# MD201__1.net
KiCad netlist of a schematic drawn in EAGLE
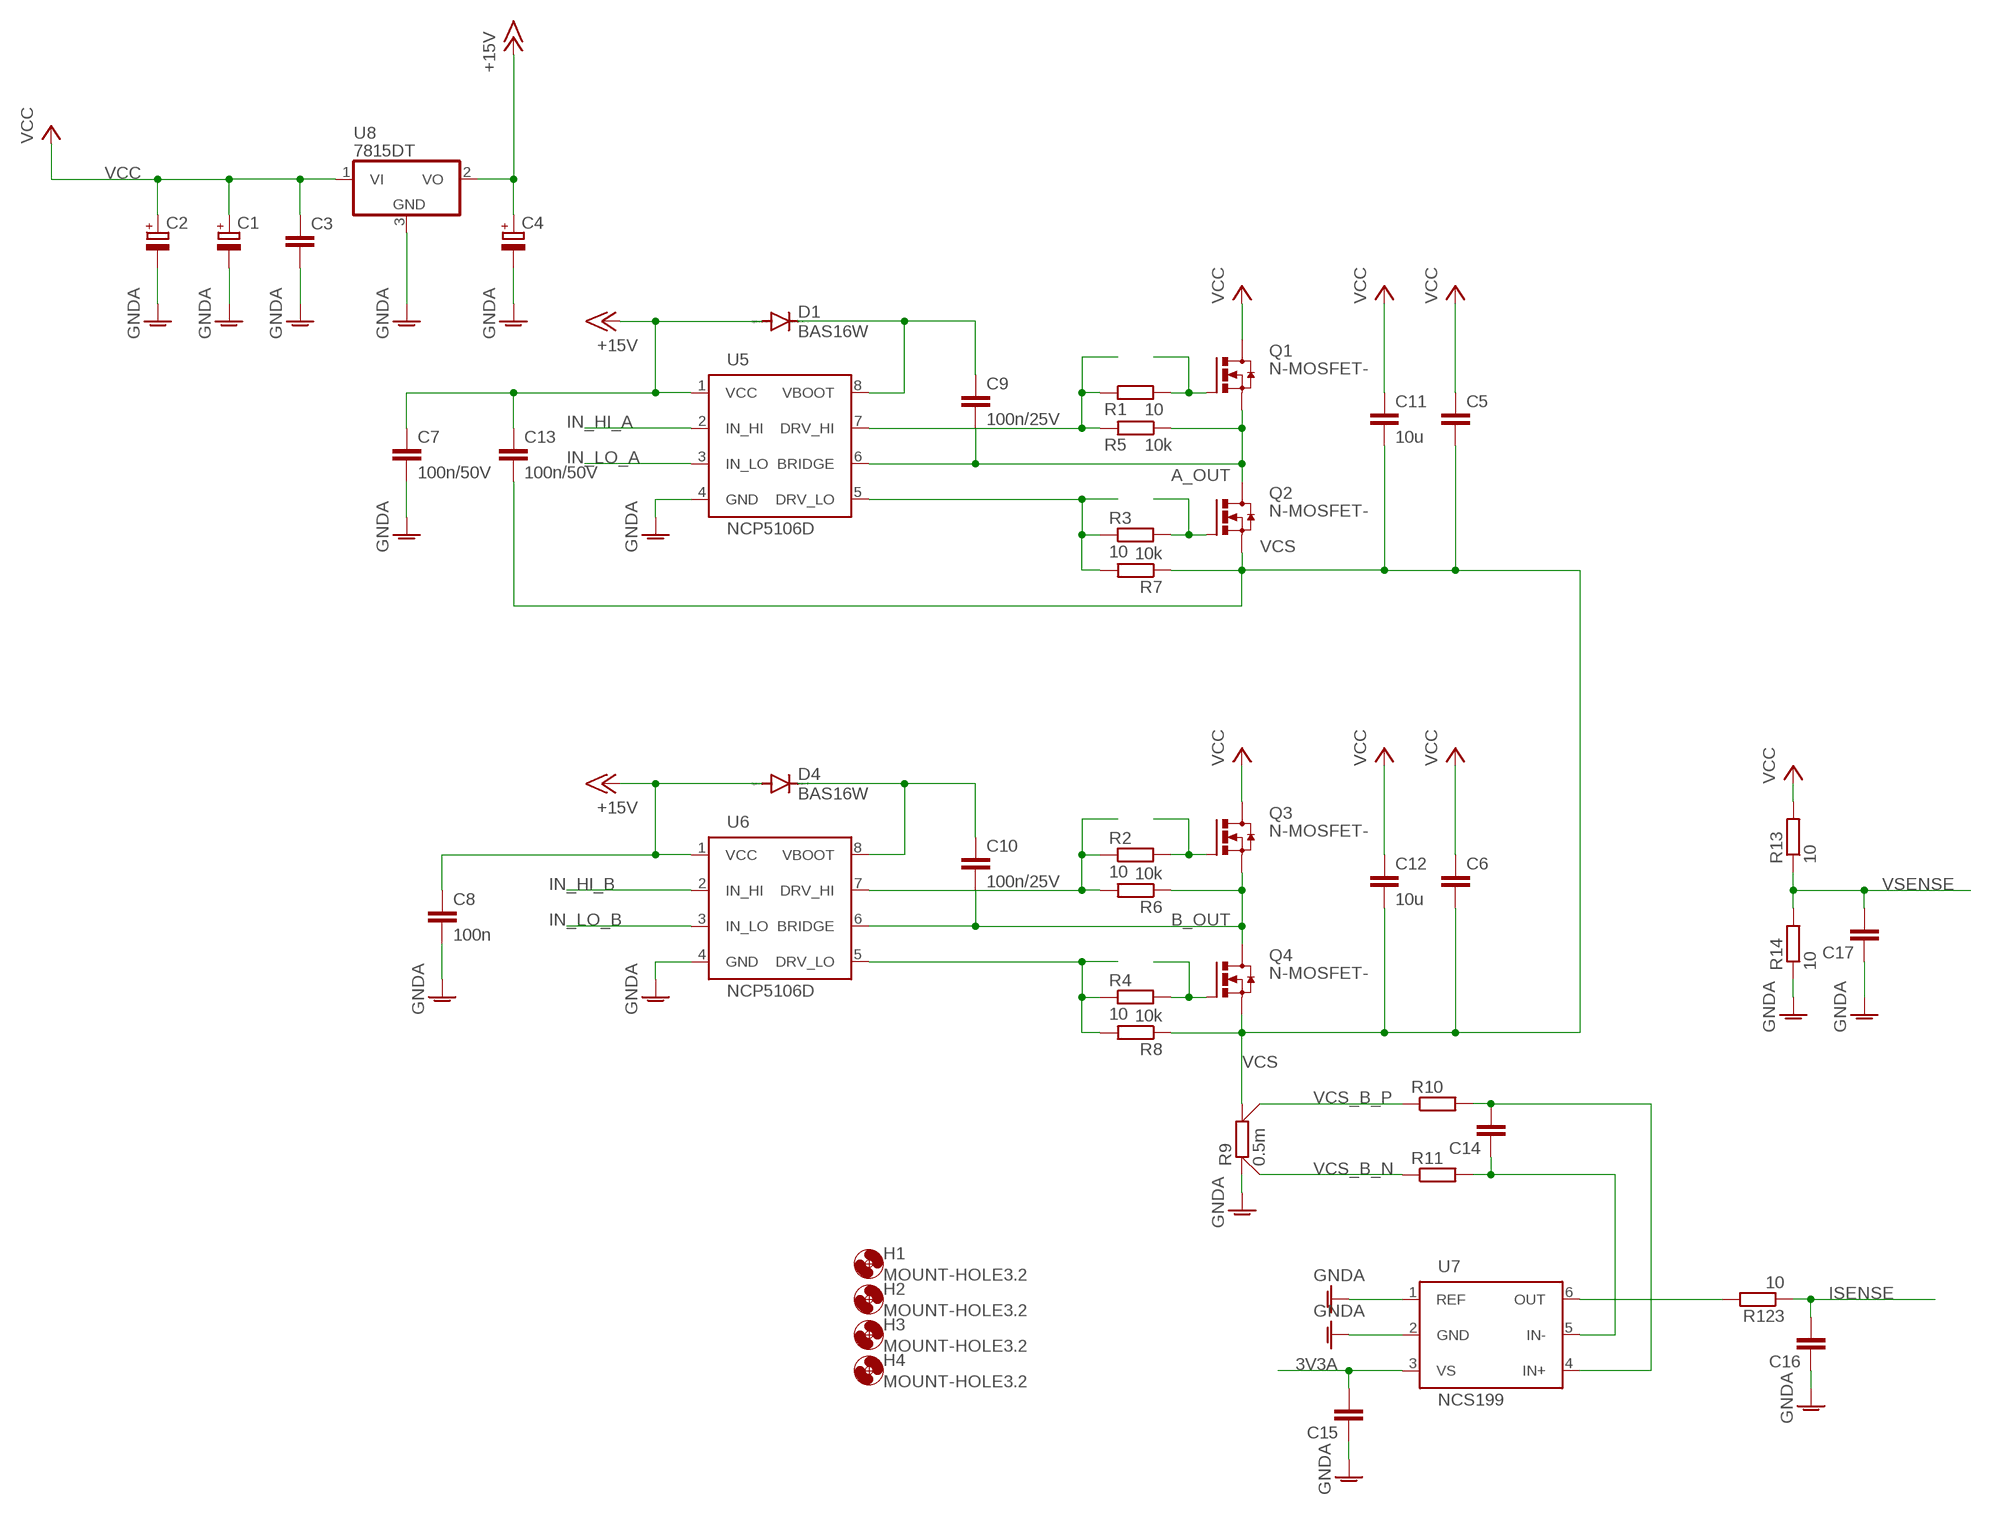
[diagram p0: schematic, sheet 1]
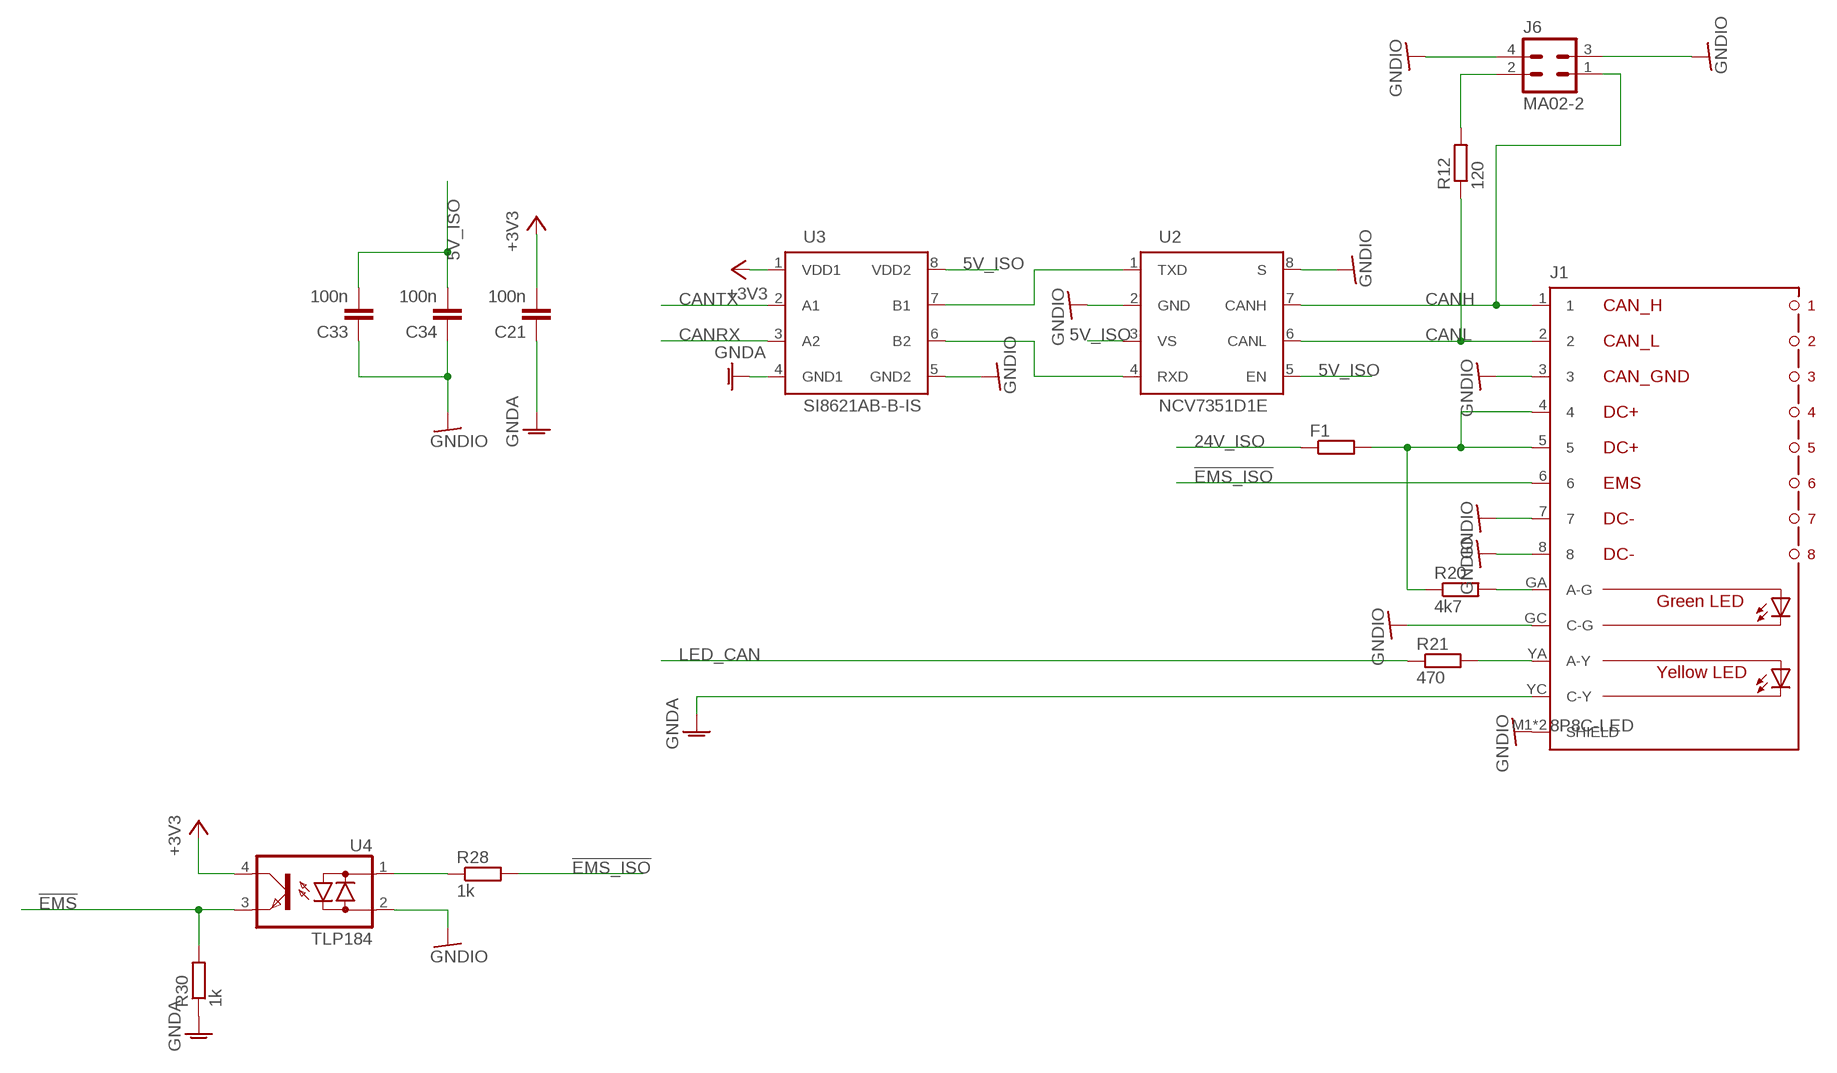
[diagram p1: schematic, sheet 2]
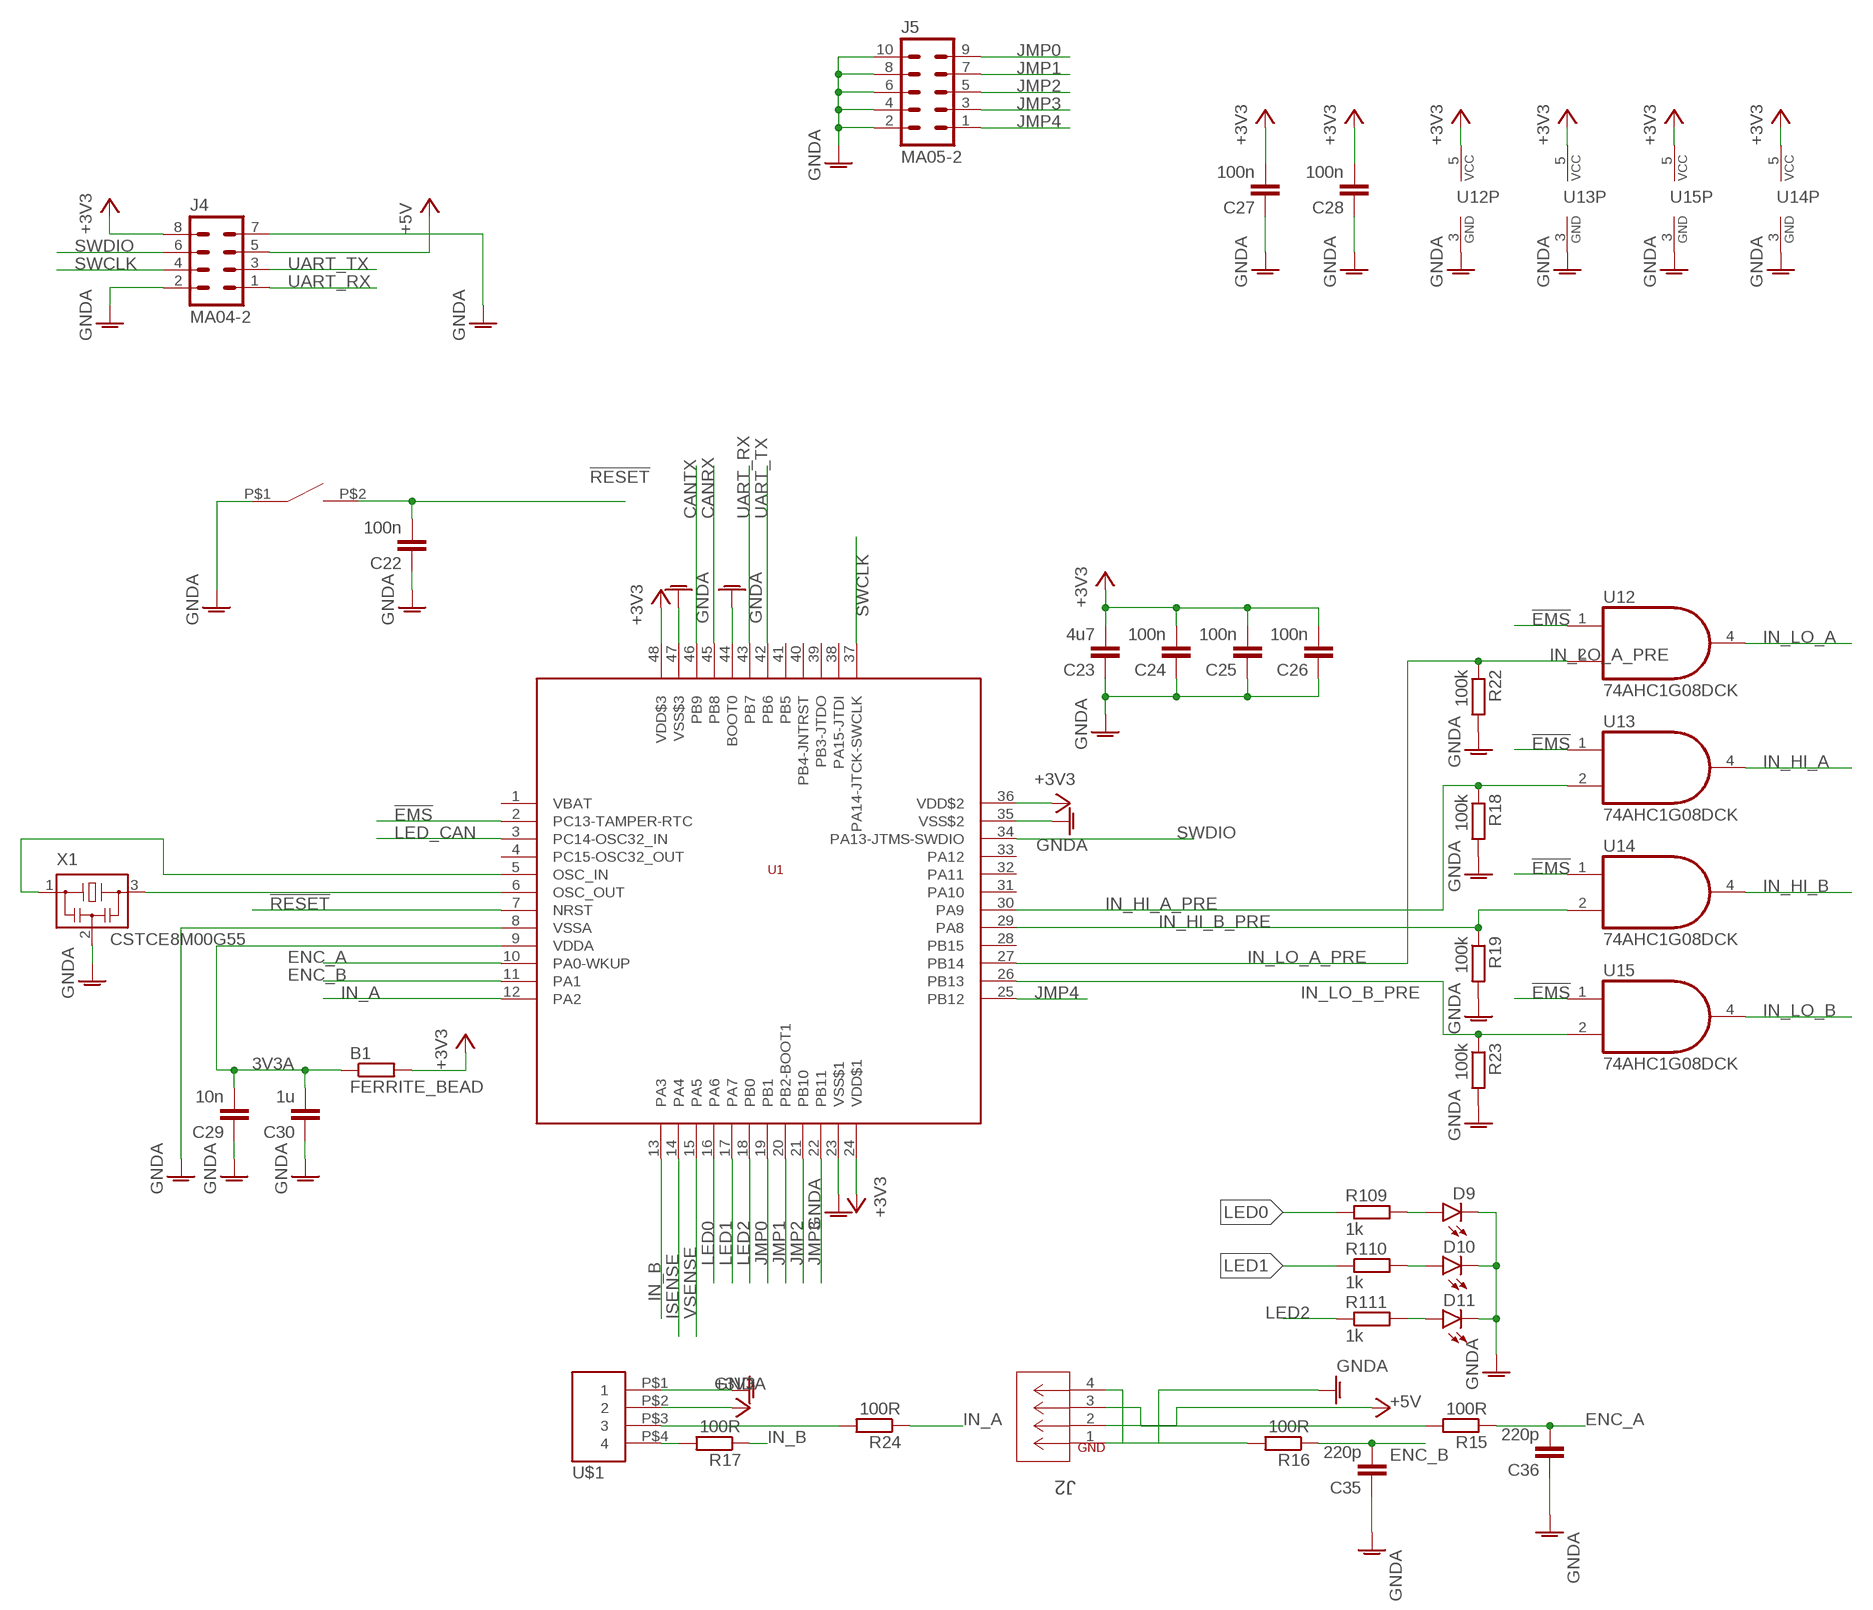
[diagram p2: schematic, sheet 3]
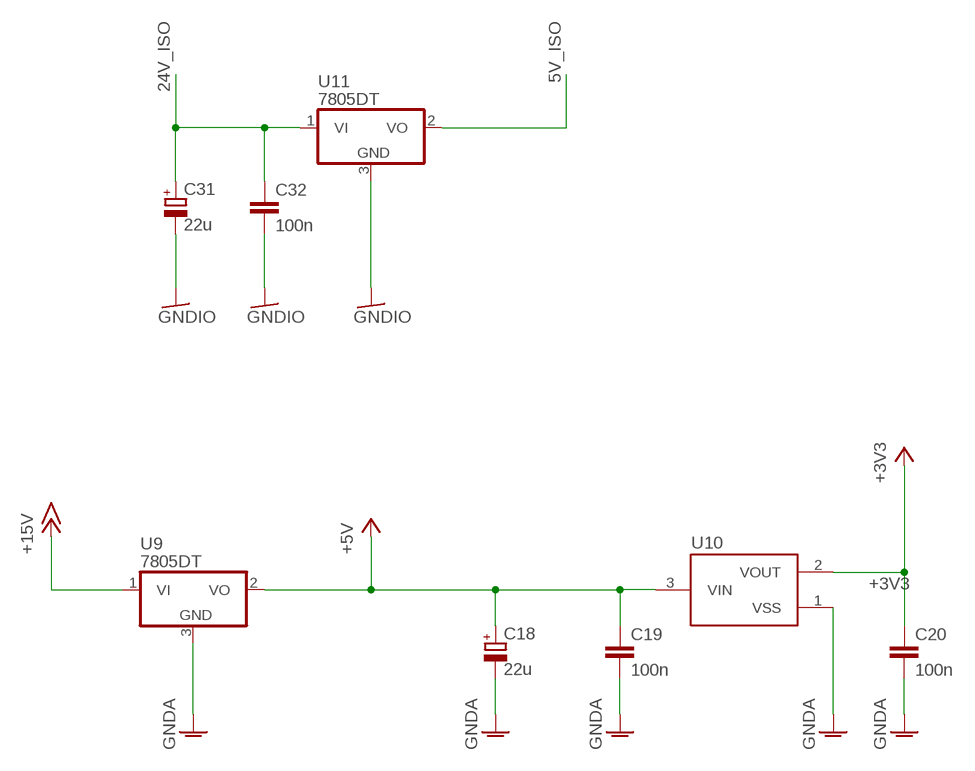
[diagram p3: schematic, sheet 4]

(export (version "E")
  (design (tool "Eeschema 10.0.6"))
  (components
    (comp (ref "C21")
      (value "100n")
      (footprint "eagle-import:C0603")
      (libsource (lib "eagle-import") (part "C-EUC0603"))
    )
    (comp (ref "C33")
      (value "100n")
      (footprint "eagle-import:C0805")
      (libsource (lib "eagle-import") (part "C-EUC0805"))
    )
    (comp (ref "C34")
      (value "100n")
      (footprint "eagle-import:C0603")
      (libsource (lib "eagle-import") (part "C-EUC0603"))
    )
    (comp (ref "F1")
      (value "R-EU_R1206")
      (footprint "eagle-import:R1206")
      (libsource (lib "eagle-import") (part "rcl_334_R-EU_R1206"))
    )
    (comp (ref "J1")
      (value "8P8C-LED")
      (footprint "eagle-import:8P8C-LED")
      (libsource (lib "eagle-import") (part "8P8C-LED"))
    )
    (comp (ref "J6")
      (value "MA02-2")
      (footprint "eagle-import:MA02-2W")
      (libsource (lib "eagle-import") (part "MA02-2"))
    )
    (comp (ref "R12")
      (value "120")
      (footprint "eagle-import:R0603")
      (libsource (lib "eagle-import") (part "rcl_334_R-EU_R0603"))
    )
    (comp (ref "R20")
      (value "4k7")
      (footprint "eagle-import:R0603")
      (libsource (lib "eagle-import") (part "rcl_334_R-EU_R0603"))
    )
    (comp (ref "R21")
      (value "470")
      (footprint "eagle-import:R0603")
      (libsource (lib "eagle-import") (part "rcl_334_R-EU_R0603"))
    )
    (comp (ref "R28")
      (value "1k")
      (footprint "eagle-import:R0603")
      (libsource (lib "eagle-import") (part "rcl_334_R-EU_R0603"))
    )
    (comp (ref "R30")
      (value "1k")
      (footprint "eagle-import:R0603")
      (libsource (lib "eagle-import") (part "rcl_334_R-EU_R0603"))
    )
    (comp (ref "U2")
      (value "NCV7351D1E")
      (footprint "eagle-import:SO08")
      (libsource (lib "eagle-import") (part "NCV7351D1E"))
    )
    (comp (ref "U3")
      (value "SI8621AB-B-IS")
      (footprint "eagle-import:SO08")
      (libsource (lib "eagle-import") (part "SI8621AB-B-IS"))
    )
    (comp (ref "U4")
      (value "TLP184")
      (footprint "eagle-import:11-4M1S")
      (libsource (lib "eagle-import") (part "TLP184"))
    )
    (comp (ref "C18")
      (value "22u")
      (footprint "eagle-import:E2,5-5")
      (libsource (lib "eagle-import") (part "CPOL-EUE2.5-5"))
    )
    (comp (ref "C19")
      (value "100n")
      (footprint "eagle-import:C0603")
      (libsource (lib "eagle-import") (part "C-EUC0603"))
    )
    (comp (ref "C20")
      (value "100n")
      (footprint "eagle-import:C0603")
      (libsource (lib "eagle-import") (part "C-EUC0603"))
    )
    (comp (ref "C31")
      (value "22u")
      (footprint "eagle-import:E2,5-5")
      (libsource (lib "eagle-import") (part "CPOL-EUE2.5-5"))
    )
    (comp (ref "C32")
      (value "100n")
      (footprint "eagle-import:C0603")
      (libsource (lib "eagle-import") (part "C-EUC0603"))
    )
    (comp (ref "U9")
      (value "7805DT")
      (footprint "eagle-import:TO252")
      (libsource (lib "eagle-import") (part "78DT05"))
    )
    (comp (ref "U10")
      (value "XC6206")
      (footprint "eagle-import:SOT95P240X110-3")
      (libsource (lib "eagle-import") (part "XC6206"))
    )
    (comp (ref "U11")
      (value "7805DT")
      (footprint "eagle-import:TO252")
      (libsource (lib "eagle-import") (part "78DT05"))
    )
    (comp (ref "B1")
      (value "FERRITE_BEAD")
      (footprint "eagle-import:R0603")
      (libsource (lib "eagle-import") (part "R-EU_R0603"))
    )
    (comp (ref "C22")
      (value "100n")
      (footprint "eagle-import:C0603")
      (libsource (lib "eagle-import") (part "C-EUC0603"))
    )
    (comp (ref "C23")
      (value "4u7")
      (footprint "eagle-import:C0805")
      (libsource (lib "eagle-import") (part "C-EUC0805"))
    )
    (comp (ref "C24")
      (value "100n")
      (footprint "eagle-import:C0603")
      (libsource (lib "eagle-import") (part "C-EUC0603"))
    )
    (comp (ref "C25")
      (value "100n")
      (footprint "eagle-import:C0603")
      (libsource (lib "eagle-import") (part "C-EUC0603"))
    )
    (comp (ref "C26")
      (value "100n")
      (footprint "eagle-import:C0603")
      (libsource (lib "eagle-import") (part "C-EUC0603"))
    )
    (comp (ref "C27")
      (value "100n")
      (footprint "eagle-import:C0603")
      (libsource (lib "eagle-import") (part "C-EUC0603"))
    )
    (comp (ref "C28")
      (value "100n")
      (footprint "eagle-import:C0603")
      (libsource (lib "eagle-import") (part "C-EUC0603"))
    )
    (comp (ref "C29")
      (value "10n")
      (footprint "eagle-import:C0603")
      (libsource (lib "eagle-import") (part "C-EUC0603"))
    )
    (comp (ref "C30")
      (value "1u")
      (footprint "eagle-import:C0603")
      (libsource (lib "eagle-import") (part "C-EUC0603"))
    )
    (comp (ref "C35")
      (value "220p")
      (footprint "eagle-import:C0603")
      (libsource (lib "eagle-import") (part "C-EUC0603"))
    )
    (comp (ref "C36")
      (value "220p")
      (footprint "eagle-import:C0603")
      (libsource (lib "eagle-import") (part "C-EUC0603"))
    )
    (comp (ref "D9")
      (value "LEDCHIPLED_0805")
      (footprint "eagle-import:CHIPLED_0805")
      (libsource (lib "eagle-import") (part "LEDCHIPLED_0805"))
    )
    (comp (ref "D10")
      (value "LEDCHIPLED_0805")
      (footprint "eagle-import:CHIPLED_0805")
      (libsource (lib "eagle-import") (part "LEDCHIPLED_0805"))
    )
    (comp (ref "D11")
      (value "LEDCHIPLED_0805")
      (footprint "eagle-import:CHIPLED_0805")
      (libsource (lib "eagle-import") (part "LEDCHIPLED_0805"))
    )
    (comp (ref "J2")
      (value "1744426-4")
      (footprint "eagle-import:CONN4_1744426-4")
      (fields (field (name "MANUFACTURER_PART_NUMBER") "17444264"))
      (libsource (lib "eagle-import") (part "1744426-4"))
    )
    (comp (ref "J4")
      (value "MA04-2")
      (footprint "eagle-import:MA04-2W")
      (libsource (lib "eagle-import") (part "MA04-2"))
    )
    (comp (ref "J5")
      (value "MA05-2")
      (footprint "eagle-import:MA05-2W")
      (libsource (lib "eagle-import") (part "MA05-2"))
    )
    (comp (ref "R15")
      (value "100R")
      (footprint "eagle-import:R0603")
      (libsource (lib "eagle-import") (part "R-EU_R0603"))
    )
    (comp (ref "R16")
      (value "100R")
      (footprint "eagle-import:R0603")
      (libsource (lib "eagle-import") (part "R-EU_R0603"))
    )
    (comp (ref "R17")
      (value "100R")
      (footprint "eagle-import:R0603")
      (libsource (lib "eagle-import") (part "R-EU_R0603"))
    )
    (comp (ref "R18")
      (value "100k")
      (footprint "eagle-import:R0603")
      (libsource (lib "eagle-import") (part "R-EU_R0603"))
    )
    (comp (ref "R19")
      (value "100k")
      (footprint "eagle-import:R0603")
      (libsource (lib "eagle-import") (part "R-EU_R0603"))
    )
    (comp (ref "R22")
      (value "100k")
      (footprint "eagle-import:R0603")
      (libsource (lib "eagle-import") (part "R-EU_R0603"))
    )
    (comp (ref "R23")
      (value "100k")
      (footprint "eagle-import:R0603")
      (libsource (lib "eagle-import") (part "R-EU_R0603"))
    )
    (comp (ref "R24")
      (value "100R")
      (footprint "eagle-import:R0603")
      (libsource (lib "eagle-import") (part "R-EU_R0603"))
    )
    (comp (ref "R109")
      (value "1k")
      (footprint "eagle-import:R0603")
      (libsource (lib "eagle-import") (part "R-EU_R0603"))
    )
    (comp (ref "R110")
      (value "1k")
      (footprint "eagle-import:R0603")
      (libsource (lib "eagle-import") (part "R-EU_R0603"))
    )
    (comp (ref "R111")
      (value "1k")
      (footprint "eagle-import:R0603")
      (libsource (lib "eagle-import") (part "R-EU_R0603"))
    )
    (comp (ref "S1")
      (value "SWITCH_TACTILETOP")
      (footprint "eagle-import:SWITCH_TACTILE_3X6")
      (libsource (lib "eagle-import") (part "SWITCH_TACTILETOP"))
    )
    (comp (ref "U$1")
      (value "XH-4-SIDE")
      (footprint "eagle-import:CON-XH-4-SIDE")
      (libsource (lib "eagle-import") (part "XH-4-SIDE"))
    )
    (comp (ref "U1")
      (value "STM32F103C8")
      (footprint "eagle-import:LQFP48")
      (libsource (lib "eagle-import") (part "STM32F103C8"))
    )
    (comp (ref "U12")
      (value "74AHC1G08DCK")
      (footprint "eagle-import:SC70-5")
      (libsource (lib "eagle-import") (part "741G08DCKAHC"))
    )
    (comp (ref "U13")
      (value "74AHC1G08DCK")
      (footprint "eagle-import:SC70-5")
      (libsource (lib "eagle-import") (part "741G08DCKAHC"))
    )
    (comp (ref "U14")
      (value "74AHC1G08DCK")
      (footprint "eagle-import:SC70-5")
      (libsource (lib "eagle-import") (part "741G08DCKAHC"))
    )
    (comp (ref "U15")
      (value "74AHC1G08DCK")
      (footprint "eagle-import:SC70-5")
      (libsource (lib "eagle-import") (part "741G08DCKAHC"))
    )
    (comp (ref "X1")
      (value "CSTCE8M00G55")
      (footprint "eagle-import:CSTCE8M00G55")
      (libsource (lib "eagle-import") (part "CSTCE8M00G55"))
    )
    (comp (ref "C1")
      (value "CPOL-EUE5-10.5")
      (footprint "eagle-import:E5-10,5")
      (libsource (lib "eagle-import") (part "CPOL-EUE5-10.5"))
    )
    (comp (ref "C2")
      (value "CPOL-EUE5-10.5")
      (footprint "eagle-import:E5-10,5")
      (libsource (lib "eagle-import") (part "CPOL-EUE5-10.5"))
    )
    (comp (ref "C3")
      (value "C-EUC0603")
      (footprint "eagle-import:C0603")
      (libsource (lib "eagle-import") (part "C-EUC0603"))
    )
    (comp (ref "C4")
      (value "CPOL-EUE2.5-5")
      (footprint "eagle-import:E2,5-5")
      (libsource (lib "eagle-import") (part "CPOL-EUE2.5-5"))
    )
    (comp (ref "C5")
      (value "C-EUC0603")
      (footprint "eagle-import:C0603")
      (libsource (lib "eagle-import") (part "C-EUC0603"))
    )
    (comp (ref "C6")
      (value "C-EUC0603")
      (footprint "eagle-import:C0603")
      (libsource (lib "eagle-import") (part "C-EUC0603"))
    )
    (comp (ref "C7")
      (value "100n/50V")
      (footprint "eagle-import:C0603")
      (libsource (lib "eagle-import") (part "C-EUC0603"))
    )
    (comp (ref "C8")
      (value "100n")
      (footprint "eagle-import:C0603")
      (libsource (lib "eagle-import") (part "C-EUC0603"))
    )
    (comp (ref "C9")
      (value "100n/25V")
      (footprint "eagle-import:C0603")
      (libsource (lib "eagle-import") (part "C-EUC0603"))
    )
    (comp (ref "C10")
      (value "100n/25V")
      (footprint "eagle-import:C0603")
      (libsource (lib "eagle-import") (part "C-EUC0603"))
    )
    (comp (ref "C11")
      (value "10u")
      (footprint "eagle-import:C1210")
      (libsource (lib "eagle-import") (part "C-EUC1210"))
    )
    (comp (ref "C12")
      (value "10u")
      (footprint "eagle-import:C1210")
      (libsource (lib "eagle-import") (part "C-EUC1210"))
    )
    (comp (ref "C13")
      (value "100n/50V")
      (footprint "eagle-import:C0603")
      (libsource (lib "eagle-import") (part "C-EUC0603"))
    )
    (comp (ref "C14")
      (value "C-EUC0603")
      (footprint "eagle-import:C0603")
      (libsource (lib "eagle-import") (part "rcl_334_C-EUC0603"))
    )
    (comp (ref "C15")
      (value "C-EUC0603")
      (footprint "eagle-import:C0603")
      (libsource (lib "eagle-import") (part "rcl_334_C-EUC0603"))
    )
    (comp (ref "C16")
      (value "C-EUC0603")
      (footprint "eagle-import:C0603")
      (libsource (lib "eagle-import") (part "rcl_334_C-EUC0603"))
    )
    (comp (ref "C17")
      (value "C-EUC0603")
      (footprint "eagle-import:C0603")
      (libsource (lib "eagle-import") (part "rcl_334_C-EUC0603"))
    )
    (comp (ref "D1")
      (value "BAS16W")
      (footprint "eagle-import:SOD323-R")
      (libsource (lib "eagle-import") (part "DIODE-SOD323-R"))
    )
    (comp (ref "D4")
      (value "BAS16W")
      (footprint "eagle-import:SOD323-R")
      (libsource (lib "eagle-import") (part "DIODE-SOD323-R"))
    )
    (comp (ref "H1")
      (value "MOUNT-HOLE3.2")
      (footprint "eagle-import:3,2")
      (libsource (lib "eagle-import") (part "MOUNT-HOLE3.2"))
    )
    (comp (ref "H2")
      (value "MOUNT-HOLE3.2")
      (footprint "eagle-import:3,2")
      (libsource (lib "eagle-import") (part "MOUNT-HOLE3.2"))
    )
    (comp (ref "H3")
      (value "MOUNT-HOLE3.2")
      (footprint "eagle-import:3,2")
      (libsource (lib "eagle-import") (part "MOUNT-HOLE3.2"))
    )
    (comp (ref "H4")
      (value "MOUNT-HOLE3.2")
      (footprint "eagle-import:3,2")
      (libsource (lib "eagle-import") (part "MOUNT-HOLE3.2"))
    )
    (comp (ref "Q1")
      (value "N-MOSFET-")
      (footprint "eagle-import:SOT669")
      (libsource (lib "eagle-import") (part "N-MOSFET-"))
    )
    (comp (ref "Q2")
      (value "N-MOSFET-")
      (footprint "eagle-import:SOT669")
      (libsource (lib "eagle-import") (part "N-MOSFET-"))
    )
    (comp (ref "Q3")
      (value "N-MOSFET-")
      (footprint "eagle-import:SOT669")
      (libsource (lib "eagle-import") (part "N-MOSFET-"))
    )
    (comp (ref "Q4")
      (value "N-MOSFET-")
      (footprint "eagle-import:SOT669")
      (libsource (lib "eagle-import") (part "N-MOSFET-"))
    )
    (comp (ref "R1")
      (value "10")
      (footprint "eagle-import:R0603")
      (libsource (lib "eagle-import") (part "R-EU_R0603"))
    )
    (comp (ref "R2")
      (value "10")
      (footprint "eagle-import:R0603")
      (libsource (lib "eagle-import") (part "R-EU_R0603"))
    )
    (comp (ref "R3")
      (value "10")
      (footprint "eagle-import:R0603")
      (libsource (lib "eagle-import") (part "R-EU_R0603"))
    )
    (comp (ref "R4")
      (value "10")
      (footprint "eagle-import:R0603")
      (libsource (lib "eagle-import") (part "R-EU_R0603"))
    )
    (comp (ref "R5")
      (value "10k")
      (footprint "eagle-import:R0603")
      (libsource (lib "eagle-import") (part "R-EU_R0603"))
    )
    (comp (ref "R6")
      (value "10k")
      (footprint "eagle-import:R0603")
      (libsource (lib "eagle-import") (part "R-EU_R0603"))
    )
    (comp (ref "R7")
      (value "10k")
      (footprint "eagle-import:R0603")
      (libsource (lib "eagle-import") (part "R-EU_R0603"))
    )
    (comp (ref "R8")
      (value "10k")
      (footprint "eagle-import:R0603")
      (libsource (lib "eagle-import") (part "R-EU_R0603"))
    )
    (comp (ref "R9")
      (value "0.5m")
      (footprint "eagle-import:CSS2H-2512")
      (libsource (lib "eagle-import") (part "CSS2H-2512"))
    )
    (comp (ref "R10")
      (value "R-EU_R0603")
      (footprint "eagle-import:R0603")
      (libsource (lib "eagle-import") (part "rcl_334_R-EU_R0603"))
    )
    (comp (ref "R11")
      (value "R-EU_R0603")
      (footprint "eagle-import:R0603")
      (libsource (lib "eagle-import") (part "rcl_334_R-EU_R0603"))
    )
    (comp (ref "R13")
      (value "10")
      (footprint "eagle-import:R0603")
      (libsource (lib "eagle-import") (part "R-EU_R0603"))
    )
    (comp (ref "R14")
      (value "10")
      (footprint "eagle-import:R0603")
      (libsource (lib "eagle-import") (part "R-EU_R0603"))
    )
    (comp (ref "R123")
      (value "10")
      (footprint "eagle-import:R0603")
      (libsource (lib "eagle-import") (part "R-EU_R0603"))
    )
    (comp (ref "U5")
      (value "NCP5106D")
      (footprint "eagle-import:SOIC127P600X175-8")
      (libsource (lib "eagle-import") (part "NCP5106D"))
    )
    (comp (ref "U6")
      (value "NCP5106D")
      (footprint "eagle-import:SOIC127P600X175-8")
      (libsource (lib "eagle-import") (part "NCP5106D"))
    )
    (comp (ref "U7")
      (value "NCS199")
      (footprint "eagle-import:SOT65P210X110-6")
      (libsource (lib "eagle-import") (part "NCS199"))
    )
    (comp (ref "U8")
      (value "7815DT")
      (footprint "eagle-import:TO252")
      (libsource (lib "eagle-import") (part "78DT15"))
    )
  )
  (nets
    (net (code "1") (name "+3V3") (class "Default")
      (node (ref "B1") (pin "2") (pinfunction "2_2") (pintype "passive"))
      (node (ref "C20") (pin "1") (pinfunction "1_1") (pintype "passive"))
      (node (ref "C21") (pin "2") (pinfunction "2_2") (pintype "passive"))
      (node (ref "C23") (pin "2") (pinfunction "2_2") (pintype "passive"))
      (node (ref "C24") (pin "2") (pinfunction "2_2") (pintype "passive"))
      (node (ref "C25") (pin "2") (pinfunction "2_2") (pintype "passive"))
      (node (ref "C26") (pin "2") (pinfunction "2_2") (pintype "passive"))
      (node (ref "C27") (pin "2") (pinfunction "2_2") (pintype "passive"))
      (node (ref "C28") (pin "2") (pinfunction "2_2") (pintype "passive"))
      (node (ref "J4") (pin "8") (pinfunction "8_8") (pintype "passive"))
      (node (ref "U$1") (pin "P$2") (pinfunction "2_P$2") (pintype "bidirectional"))
      (node (ref "U1") (pin "24") (pinfunction "VDD$1_24") (pintype "passive"))
      (node (ref "U1") (pin "36") (pinfunction "VDD$2_36") (pintype "passive"))
      (node (ref "U1") (pin "48") (pinfunction "VDD$3_48") (pintype "passive"))
      (node (ref "U10") (pin "2") (pinfunction "VOUT_2") (pintype "bidirectional"))
      (node (ref "U12") (pin "5") (pinfunction "VCC_5") (pintype "power_in"))
      (node (ref "U13") (pin "5") (pinfunction "VCC_5") (pintype "power_in"))
      (node (ref "U14") (pin "5") (pinfunction "VCC_5") (pintype "power_in"))
      (node (ref "U15") (pin "5") (pinfunction "VCC_5") (pintype "power_in"))
      (node (ref "U3") (pin "1") (pinfunction "VDD1_1") (pintype "power_in"))
      (node (ref "U4") (pin "4") (pinfunction "C_4") (pintype "passive"))
    )
    (net (code "2") (name "+5V") (class "Default")
      (node (ref "C18") (pin "+") (pinfunction "+_+") (pintype "passive"))
      (node (ref "C19") (pin "1") (pinfunction "1_1") (pintype "passive"))
      (node (ref "J2") (pin "2") (pinfunction "2_2") (pintype "passive"))
      (node (ref "J4") (pin "5") (pinfunction "5_5") (pintype "passive"))
      (node (ref "U10") (pin "3") (pinfunction "VIN_3") (pintype "bidirectional"))
      (node (ref "U9") (pin "2") (pinfunction "VO_2") (pintype "passive"))
    )
    (net (code "3") (name "+15V") (class "Default")
      (node (ref "C13") (pin "1") (pinfunction "1_1") (pintype "passive"))
      (node (ref "C4") (pin "+") (pinfunction "+_+") (pintype "passive"))
      (node (ref "C7") (pin "1") (pinfunction "1_1") (pintype "passive"))
      (node (ref "C8") (pin "1") (pinfunction "1_1") (pintype "passive"))
      (node (ref "D1") (pin "A") (pinfunction "A_A") (pintype "passive"))
      (node (ref "D4") (pin "A") (pinfunction "A_A") (pintype "passive"))
      (node (ref "U5") (pin "1") (pinfunction "VCC_1") (pintype "power_in"))
      (node (ref "U6") (pin "1") (pinfunction "VCC_1") (pintype "power_in"))
      (node (ref "U8") (pin "2") (pinfunction "VO_2") (pintype "passive"))
      (node (ref "U9") (pin "1") (pinfunction "VI_1") (pintype "input"))
    )
    (net (code "4") (name "3V3A") (class "Default")
      (node (ref "B1") (pin "1") (pinfunction "1_1") (pintype "passive"))
      (node (ref "C15") (pin "2") (pinfunction "2_2") (pintype "passive"))
      (node (ref "C29") (pin "2") (pinfunction "2_2") (pintype "passive"))
      (node (ref "C30") (pin "2") (pinfunction "2_2") (pintype "passive"))
      (node (ref "U1") (pin "9") (pinfunction "VDDA_9") (pintype "bidirectional"))
      (node (ref "U7") (pin "3") (pinfunction "VS_3") (pintype "power_in"))
    )
    (net (code "5") (name "5V_ISO") (class "Default")
      (node (ref "C33") (pin "2") (pinfunction "2_2") (pintype "passive"))
      (node (ref "C34") (pin "2") (pinfunction "2_2") (pintype "passive"))
      (node (ref "U11") (pin "2") (pinfunction "VO_2") (pintype "passive"))
      (node (ref "U2") (pin "3") (pinfunction "VS_3") (pintype "power_in"))
      (node (ref "U2") (pin "5") (pinfunction "EN_5") (pintype "input"))
      (node (ref "U3") (pin "8") (pinfunction "VDD2_8") (pintype "power_in"))
    )
    (net (code "6") (name "24V_ISO") (class "Default")
      (node (ref "C31") (pin "+") (pinfunction "+_+") (pintype "passive"))
      (node (ref "C32") (pin "1") (pinfunction "1_1") (pintype "passive"))
      (node (ref "F1") (pin "1") (pinfunction "1_1") (pintype "passive"))
      (node (ref "U11") (pin "1") (pinfunction "VI_1") (pintype "input"))
    )
    (net (code "7") (name "A_OUT") (class "Default")
      (node (ref "C9") (pin "2") (pinfunction "2_2") (pintype "passive"))
      (node (ref "Q1") (pin "1") (pinfunction "SOURCE_1") (pintype "passive"))
      (node (ref "Q1") (pin "2") (pinfunction "SOURCE_2") (pintype "passive"))
      (node (ref "Q1") (pin "3") (pinfunction "SOURCE_3") (pintype "passive"))
      (node (ref "Q2") (pin "5") (pinfunction "DRAIN_5") (pintype "passive"))
      (node (ref "R5") (pin "1") (pinfunction "1_1") (pintype "passive"))
      (node (ref "U5") (pin "6") (pinfunction "BRIDGE_6") (pintype "power_in"))
    )
    (net (code "8") (name "B_OUT") (class "Default")
      (node (ref "C10") (pin "2") (pinfunction "2_2") (pintype "passive"))
      (node (ref "Q3") (pin "1") (pinfunction "SOURCE_1") (pintype "passive"))
      (node (ref "Q3") (pin "2") (pinfunction "SOURCE_2") (pintype "passive"))
      (node (ref "Q3") (pin "3") (pinfunction "SOURCE_3") (pintype "passive"))
      (node (ref "Q4") (pin "5") (pinfunction "DRAIN_5") (pintype "passive"))
      (node (ref "R6") (pin "1") (pinfunction "1_1") (pintype "passive"))
      (node (ref "U6") (pin "6") (pinfunction "BRIDGE_6") (pintype "power_in"))
    )
    (net (code "9") (name "CANH") (class "Default")
      (node (ref "J1") (pin "1") (pinfunction "1_1") (pintype "input"))
      (node (ref "J6") (pin "1") (pinfunction "1_1") (pintype "passive"))
      (node (ref "U2") (pin "7") (pinfunction "CANH_7") (pintype "output"))
    )
    (net (code "10") (name "CANL") (class "Default")
      (node (ref "J1") (pin "2") (pinfunction "2_2") (pintype "input"))
      (node (ref "R12") (pin "1") (pinfunction "1_1") (pintype "passive"))
      (node (ref "U2") (pin "6") (pinfunction "CANL_6") (pintype "output"))
    )
    (net (code "11") (name "CANRX") (class "Default")
      (node (ref "U1") (pin "45") (pinfunction "PB8_45") (pintype "bidirectional"))
      (node (ref "U3") (pin "3") (pinfunction "A2_3") (pintype "output"))
    )
    (net (code "12") (name "CANTX") (class "Default")
      (node (ref "U1") (pin "46") (pinfunction "PB9_46") (pintype "bidirectional"))
      (node (ref "U3") (pin "2") (pinfunction "A1_2") (pintype "input"))
    )
    (net (code "13") (name "ENC_A") (class "Default")
      (node (ref "C36") (pin "2") (pinfunction "2_2") (pintype "passive"))
      (node (ref "R15") (pin "1") (pinfunction "1_1") (pintype "passive"))
      (node (ref "U1") (pin "10") (pinfunction "PA0-WKUP_10") (pintype "bidirectional"))
    )
    (net (code "14") (name "ENC_B") (class "Default")
      (node (ref "C35") (pin "2") (pinfunction "2_2") (pintype "passive"))
      (node (ref "R16") (pin "1") (pinfunction "1_1") (pintype "passive"))
      (node (ref "U1") (pin "11") (pinfunction "PA1_11") (pintype "bidirectional"))
    )
    (net (code "15") (name "GNDA") (class "Default")
      (node (ref "C1") (pin "-") (pinfunction "-_-") (pintype "passive"))
      (node (ref "C15") (pin "1") (pinfunction "1_1") (pintype "passive"))
      (node (ref "C16") (pin "1") (pinfunction "1_1") (pintype "passive"))
      (node (ref "C17") (pin "1") (pinfunction "1_1") (pintype "passive"))
      (node (ref "C18") (pin "-") (pinfunction "-_-") (pintype "passive"))
      (node (ref "C19") (pin "2") (pinfunction "2_2") (pintype "passive"))
      (node (ref "C2") (pin "-") (pinfunction "-_-") (pintype "passive"))
      (node (ref "C20") (pin "2") (pinfunction "2_2") (pintype "passive"))
      (node (ref "C21") (pin "1") (pinfunction "1_1") (pintype "passive"))
      (node (ref "C22") (pin "1") (pinfunction "1_1") (pintype "passive"))
      (node (ref "C23") (pin "1") (pinfunction "1_1") (pintype "passive"))
      (node (ref "C24") (pin "1") (pinfunction "1_1") (pintype "passive"))
      (node (ref "C25") (pin "1") (pinfunction "1_1") (pintype "passive"))
      (node (ref "C26") (pin "1") (pinfunction "1_1") (pintype "passive"))
      (node (ref "C27") (pin "1") (pinfunction "1_1") (pintype "passive"))
      (node (ref "C28") (pin "1") (pinfunction "1_1") (pintype "passive"))
      (node (ref "C29") (pin "1") (pinfunction "1_1") (pintype "passive"))
      (node (ref "C3") (pin "2") (pinfunction "2_2") (pintype "passive"))
      (node (ref "C30") (pin "1") (pinfunction "1_1") (pintype "passive"))
      (node (ref "C35") (pin "1") (pinfunction "1_1") (pintype "passive"))
      (node (ref "C36") (pin "1") (pinfunction "1_1") (pintype "passive"))
      (node (ref "C4") (pin "-") (pinfunction "-_-") (pintype "passive"))
      (node (ref "C7") (pin "2") (pinfunction "2_2") (pintype "passive"))
      (node (ref "C8") (pin "2") (pinfunction "2_2") (pintype "passive"))
      (node (ref "D10") (pin "C") (pinfunction "C_C") (pintype "passive"))
      (node (ref "D11") (pin "C") (pinfunction "C_C") (pintype "passive"))
      (node (ref "D9") (pin "C") (pinfunction "C_C") (pintype "passive"))
      (node (ref "J1") (pin "YC") (pinfunction "C-Y_YC") (pintype "passive"))
      (node (ref "J2") (pin "1") (pinfunction "1_1") (pintype "passive"))
      (node (ref "J4") (pin "2") (pinfunction "2_2") (pintype "passive"))
      (node (ref "J4") (pin "7") (pinfunction "7_7") (pintype "passive"))
      (node (ref "J5") (pin "10") (pinfunction "10_10") (pintype "passive"))
      (node (ref "J5") (pin "2") (pinfunction "2_2") (pintype "passive"))
      (node (ref "J5") (pin "4") (pinfunction "4_4") (pintype "passive"))
      (node (ref "J5") (pin "6") (pinfunction "6_6") (pintype "passive"))
      (node (ref "J5") (pin "8") (pinfunction "8_8") (pintype "passive"))
      (node (ref "R14") (pin "1") (pinfunction "1_1") (pintype "passive"))
      (node (ref "R18") (pin "2") (pinfunction "2_2") (pintype "passive"))
      (node (ref "R19") (pin "2") (pinfunction "2_2") (pintype "passive"))
      (node (ref "R22") (pin "2") (pinfunction "2_2") (pintype "passive"))
      (node (ref "R23") (pin "2") (pinfunction "2_2") (pintype "passive"))
      (node (ref "R30") (pin "1") (pinfunction "1_1") (pintype "passive"))
      (node (ref "R9") (pin "1$1") (pinfunction "1_1$1") (pintype "passive"))
      (node (ref "R9") (pin "1$2") (pinfunction "1_1$2") (pintype "passive"))
      (node (ref "S1") (pin "P$1") (pinfunction "1_P$1") (pintype "bidirectional"))
      (node (ref "U$1") (pin "P$1") (pinfunction "1_P$1") (pintype "bidirectional"))
      (node (ref "U1") (pin "23") (pinfunction "VSS$1_23") (pintype "passive"))
      (node (ref "U1") (pin "35") (pinfunction "VSS$2_35") (pintype "passive"))
      (node (ref "U1") (pin "44") (pinfunction "BOOT0_44") (pintype "input"))
      (node (ref "U1") (pin "47") (pinfunction "VSS$3_47") (pintype "passive"))
      (node (ref "U1") (pin "8") (pinfunction "VSSA_8") (pintype "bidirectional"))
      (node (ref "U10") (pin "1") (pinfunction "VSS_1") (pintype "bidirectional"))
      (node (ref "U12") (pin "3") (pinfunction "GND_3") (pintype "power_in"))
      (node (ref "U13") (pin "3") (pinfunction "GND_3") (pintype "power_in"))
      (node (ref "U14") (pin "3") (pinfunction "GND_3") (pintype "power_in"))
      (node (ref "U15") (pin "3") (pinfunction "GND_3") (pintype "power_in"))
      (node (ref "U3") (pin "4") (pinfunction "GND1_4") (pintype "power_in"))
      (node (ref "U5") (pin "4") (pinfunction "GND_4") (pintype "power_in"))
      (node (ref "U6") (pin "4") (pinfunction "GND_4") (pintype "power_in"))
      (node (ref "U7") (pin "1") (pinfunction "REF_1") (pintype "power_in"))
      (node (ref "U7") (pin "2") (pinfunction "GND_2") (pintype "power_in"))
      (node (ref "U8") (pin "3") (pinfunction "GND_3") (pintype "passive"))
      (node (ref "U9") (pin "3") (pinfunction "GND_3") (pintype "passive"))
      (node (ref "X1") (pin "2") (pinfunction "2_2") (pintype "passive"))
    )
    (net (code "16") (name "GNDIO") (class "Default")
      (node (ref "C31") (pin "-") (pinfunction "-_-") (pintype "passive"))
      (node (ref "C32") (pin "2") (pinfunction "2_2") (pintype "passive"))
      (node (ref "C33") (pin "1") (pinfunction "1_1") (pintype "passive"))
      (node (ref "C34") (pin "1") (pinfunction "1_1") (pintype "passive"))
      (node (ref "J1") (pin "3") (pinfunction "3_3") (pintype "input"))
      (node (ref "J1") (pin "7") (pinfunction "7_7") (pintype "input"))
      (node (ref "J1") (pin "8") (pinfunction "8_8") (pintype "input"))
      (node (ref "J1") (pin "GC") (pinfunction "C-G_GC") (pintype "passive"))
      (node (ref "J1") (pin "M1") (pinfunction "SHIELD_M1") (pintype "passive"))
      (node (ref "J1") (pin "M2") (pinfunction "SHIELD_M2") (pintype "passive"))
      (node (ref "J6") (pin "3") (pinfunction "3_3") (pintype "passive"))
      (node (ref "J6") (pin "4") (pinfunction "4_4") (pintype "passive"))
      (node (ref "U11") (pin "3") (pinfunction "GND_3") (pintype "passive"))
      (node (ref "U2") (pin "2") (pinfunction "GND_2") (pintype "power_in"))
      (node (ref "U2") (pin "8") (pinfunction "S_8") (pintype "input"))
      (node (ref "U3") (pin "5") (pinfunction "GND2_5") (pintype "power_in"))
      (node (ref "U4") (pin "2") (pinfunction "AC2_2") (pintype "passive"))
    )
    (net (code "17") (name "IN_A") (class "Default")
      (node (ref "R24") (pin "1") (pinfunction "1_1") (pintype "passive"))
      (node (ref "U1") (pin "12") (pinfunction "PA2_12") (pintype "bidirectional"))
    )
    (net (code "18") (name "IN_B") (class "Default")
      (node (ref "R17") (pin "1") (pinfunction "1_1") (pintype "passive"))
      (node (ref "U1") (pin "13") (pinfunction "PA3_13") (pintype "bidirectional"))
    )
    (net (code "19") (name "IN_HI_A") (class "Default")
      (node (ref "U13") (pin "4") (pinfunction "O_4") (pintype "output"))
      (node (ref "U5") (pin "2") (pinfunction "IN_HI_2") (pintype "input"))
    )
    (net (code "20") (name "IN_HI_A_PRE") (class "Default")
      (node (ref "R18") (pin "1") (pinfunction "1_1") (pintype "passive"))
      (node (ref "U1") (pin "30") (pinfunction "PA9_30") (pintype "bidirectional"))
      (node (ref "U13") (pin "2") (pinfunction "I1_2") (pintype "input"))
    )
    (net (code "21") (name "IN_HI_B") (class "Default")
      (node (ref "U14") (pin "4") (pinfunction "O_4") (pintype "output"))
      (node (ref "U6") (pin "2") (pinfunction "IN_HI_2") (pintype "input"))
    )
    (net (code "22") (name "IN_HI_B_PRE") (class "Default")
      (node (ref "R19") (pin "1") (pinfunction "1_1") (pintype "passive"))
      (node (ref "U1") (pin "29") (pinfunction "PA8_29") (pintype "bidirectional"))
      (node (ref "U14") (pin "2") (pinfunction "I1_2") (pintype "input"))
    )
    (net (code "23") (name "IN_LO_A") (class "Default")
      (node (ref "U12") (pin "4") (pinfunction "O_4") (pintype "output"))
      (node (ref "U5") (pin "3") (pinfunction "IN_LO_3") (pintype "input"))
    )
    (net (code "24") (name "IN_LO_A_PRE") (class "Default")
      (node (ref "R22") (pin "1") (pinfunction "1_1") (pintype "passive"))
      (node (ref "U1") (pin "27") (pinfunction "PB14_27") (pintype "bidirectional"))
      (node (ref "U12") (pin "2") (pinfunction "I1_2") (pintype "input"))
    )
    (net (code "25") (name "IN_LO_B") (class "Default")
      (node (ref "U15") (pin "4") (pinfunction "O_4") (pintype "output"))
      (node (ref "U6") (pin "3") (pinfunction "IN_LO_3") (pintype "input"))
    )
    (net (code "26") (name "IN_LO_B_PRE") (class "Default")
      (node (ref "R23") (pin "1") (pinfunction "1_1") (pintype "passive"))
      (node (ref "U1") (pin "26") (pinfunction "PB13_26") (pintype "bidirectional"))
      (node (ref "U15") (pin "2") (pinfunction "I1_2") (pintype "input"))
    )
    (net (code "27") (name "ISENSE") (class "Default")
      (node (ref "C16") (pin "2") (pinfunction "2_2") (pintype "passive"))
      (node (ref "R123") (pin "1") (pinfunction "1_1") (pintype "passive"))
      (node (ref "U1") (pin "14") (pinfunction "PA4_14") (pintype "bidirectional"))
    )
    (net (code "28") (name "JMP0") (class "Default")
      (node (ref "J5") (pin "9") (pinfunction "9_9") (pintype "passive"))
      (node (ref "U1") (pin "19") (pinfunction "PB1_19") (pintype "bidirectional"))
    )
    (net (code "29") (name "JMP1") (class "Default")
      (node (ref "J5") (pin "7") (pinfunction "7_7") (pintype "passive"))
      (node (ref "U1") (pin "20") (pinfunction "PB2-BOOT1_20") (pintype "bidirectional"))
    )
    (net (code "30") (name "JMP2") (class "Default")
      (node (ref "J5") (pin "5") (pinfunction "5_5") (pintype "passive"))
      (node (ref "U1") (pin "21") (pinfunction "PB10_21") (pintype "bidirectional"))
    )
    (net (code "31") (name "JMP3") (class "Default")
      (node (ref "J5") (pin "3") (pinfunction "3_3") (pintype "passive"))
      (node (ref "U1") (pin "22") (pinfunction "PB11_22") (pintype "bidirectional"))
    )
    (net (code "32") (name "JMP4") (class "Default")
      (node (ref "J5") (pin "1") (pinfunction "1_1") (pintype "passive"))
      (node (ref "U1") (pin "25") (pinfunction "PB12_25") (pintype "bidirectional"))
    )
    (net (code "33") (name "LED0") (class "Default")
      (node (ref "R109") (pin "1") (pinfunction "1_1") (pintype "passive"))
      (node (ref "U1") (pin "16") (pinfunction "PA6_16") (pintype "bidirectional"))
    )
    (net (code "34") (name "LED1") (class "Default")
      (node (ref "R110") (pin "1") (pinfunction "1_1") (pintype "passive"))
      (node (ref "U1") (pin "17") (pinfunction "PA7_17") (pintype "bidirectional"))
    )
    (net (code "35") (name "LED2") (class "Default")
      (node (ref "R111") (pin "1") (pinfunction "1_1") (pintype "passive"))
      (node (ref "U1") (pin "18") (pinfunction "PB0_18") (pintype "bidirectional"))
    )
    (net (code "36") (name "LED_CAN") (class "Default")
      (node (ref "R21") (pin "1") (pinfunction "1_1") (pintype "passive"))
      (node (ref "U1") (pin "3") (pinfunction "PC14-OSC32_IN_3") (pintype "bidirectional"))
    )
    (net (code "37") (name "Net-(D9-PadA)") (class "Default")
      (node (ref "D9") (pin "A") (pinfunction "A_A") (pintype "passive"))
      (node (ref "R109") (pin "2") (pinfunction "2_2") (pintype "passive"))
    )
    (net (code "38") (name "Net-(D10-PadA)") (class "Default")
      (node (ref "D10") (pin "A") (pinfunction "A_A") (pintype "passive"))
      (node (ref "R110") (pin "2") (pinfunction "2_2") (pintype "passive"))
    )
    (net (code "39") (name "Net-(D11-PadA)") (class "Default")
      (node (ref "D11") (pin "A") (pinfunction "A_A") (pintype "passive"))
      (node (ref "R111") (pin "2") (pinfunction "2_2") (pintype "passive"))
    )
    (net (code "40") (name "Net-(F1-Pad2)") (class "Default")
      (node (ref "F1") (pin "2") (pinfunction "2_2") (pintype "passive"))
      (node (ref "J1") (pin "4") (pinfunction "4_4") (pintype "input"))
      (node (ref "J1") (pin "5") (pinfunction "5_5") (pintype "input"))
      (node (ref "R20") (pin "1") (pinfunction "1_1") (pintype "passive"))
    )
    (net (code "41") (name "Net-(J1-A-G)") (class "Default")
      (node (ref "J1") (pin "GA") (pinfunction "A-G_GA") (pintype "passive"))
      (node (ref "R20") (pin "2") (pinfunction "2_2") (pintype "passive"))
    )
    (net (code "42") (name "Net-(J1-A-Y)") (class "Default")
      (node (ref "J1") (pin "YA") (pinfunction "A-Y_YA") (pintype "passive"))
      (node (ref "R21") (pin "2") (pinfunction "2_2") (pintype "passive"))
    )
    (net (code "43") (name "Net-(J2-Pad3)") (class "Default")
      (node (ref "J2") (pin "3") (pinfunction "3_3") (pintype "passive"))
      (node (ref "R15") (pin "2") (pinfunction "2_2") (pintype "passive"))
    )
    (net (code "44") (name "Net-(J2-Pad4)") (class "Default")
      (node (ref "J2") (pin "4") (pinfunction "4_4") (pintype "passive"))
      (node (ref "R16") (pin "2") (pinfunction "2_2") (pintype "passive"))
    )
    (net (code "45") (name "Net-(J6-Pad2)") (class "Default")
      (node (ref "J6") (pin "2") (pinfunction "2_2") (pintype "passive"))
      (node (ref "R12") (pin "2") (pinfunction "2_2") (pintype "passive"))
    )
    (net (code "46") (name "Net-(Q1-GATE)") (class "Default")
      (node (ref "Q1") (pin "4") (pinfunction "GATE_4") (pintype "passive"))
      (node (ref "R1") (pin "2") (pinfunction "2_2") (pintype "passive"))
    )
    (net (code "47") (name "Net-(Q2-GATE)") (class "Default")
      (node (ref "Q2") (pin "4") (pinfunction "GATE_4") (pintype "passive"))
      (node (ref "R3") (pin "2") (pinfunction "2_2") (pintype "passive"))
    )
    (net (code "48") (name "Net-(Q3-GATE)") (class "Default")
      (node (ref "Q3") (pin "4") (pinfunction "GATE_4") (pintype "passive"))
      (node (ref "R2") (pin "2") (pinfunction "2_2") (pintype "passive"))
    )
    (net (code "49") (name "Net-(Q4-GATE)") (class "Default")
      (node (ref "Q4") (pin "4") (pinfunction "GATE_4") (pintype "passive"))
      (node (ref "R4") (pin "2") (pinfunction "2_2") (pintype "passive"))
    )
    (net (code "50") (name "Net-(U$1-3)") (class "Default")
      (node (ref "R24") (pin "2") (pinfunction "2_2") (pintype "passive"))
      (node (ref "U$1") (pin "P$3") (pinfunction "3_P$3") (pintype "bidirectional"))
    )
    (net (code "51") (name "Net-(U$1-4)") (class "Default")
      (node (ref "R17") (pin "2") (pinfunction "2_2") (pintype "passive"))
      (node (ref "U$1") (pin "P$4") (pinfunction "4_P$4") (pintype "bidirectional"))
    )
    (net (code "52") (name "Net-(U1-OSC_IN)") (class "Default")
      (node (ref "U1") (pin "5") (pinfunction "OSC_IN_5") (pintype "input"))
      (node (ref "X1") (pin "1") (pinfunction "1_1") (pintype "passive"))
    )
    (net (code "53") (name "Net-(U1-OSC_OUT)") (class "Default")
      (node (ref "U1") (pin "6") (pinfunction "OSC_OUT_6") (pintype "output"))
      (node (ref "X1") (pin "3") (pinfunction "3_3") (pintype "passive"))
    )
    (net (code "54") (name "Net-(U2-RXD)") (class "Default")
      (node (ref "U2") (pin "4") (pinfunction "RXD_4") (pintype "output"))
      (node (ref "U3") (pin "6") (pinfunction "B2_6") (pintype "output"))
    )
    (net (code "55") (name "Net-(U2-TXD)") (class "Default")
      (node (ref "U2") (pin "1") (pinfunction "TXD_1") (pintype "input"))
      (node (ref "U3") (pin "7") (pinfunction "B1_7") (pintype "output"))
    )
    (net (code "56") (name "Net-(U4-AC1)") (class "Default")
      (node (ref "R28") (pin "1") (pinfunction "1_1") (pintype "passive"))
      (node (ref "U4") (pin "1") (pinfunction "AC1_1") (pintype "passive"))
    )
    (net (code "57") (name "Net-(U5-DRV_HI)") (class "Default")
      (node (ref "R1") (pin "1") (pinfunction "1_1") (pintype "passive"))
      (node (ref "R5") (pin "2") (pinfunction "2_2") (pintype "passive"))
      (node (ref "U5") (pin "7") (pinfunction "DRV_HI_7") (pintype "output"))
    )
    (net (code "58") (name "Net-(U5-DRV_LO)") (class "Default")
      (node (ref "R3") (pin "1") (pinfunction "1_1") (pintype "passive"))
      (node (ref "R7") (pin "2") (pinfunction "2_2") (pintype "passive"))
      (node (ref "U5") (pin "5") (pinfunction "DRV_LO_5") (pintype "output"))
    )
    (net (code "59") (name "Net-(U5-VBOOT)") (class "Default")
      (node (ref "C9") (pin "1") (pinfunction "1_1") (pintype "passive"))
      (node (ref "D1") (pin "C") (pinfunction "C_C") (pintype "passive"))
      (node (ref "U5") (pin "8") (pinfunction "VBOOT_8") (pintype "power_in"))
    )
    (net (code "60") (name "Net-(U6-DRV_HI)") (class "Default")
      (node (ref "R2") (pin "1") (pinfunction "1_1") (pintype "passive"))
      (node (ref "R6") (pin "2") (pinfunction "2_2") (pintype "passive"))
      (node (ref "U6") (pin "7") (pinfunction "DRV_HI_7") (pintype "output"))
    )
    (net (code "61") (name "Net-(U6-DRV_LO)") (class "Default")
      (node (ref "R4") (pin "1") (pinfunction "1_1") (pintype "passive"))
      (node (ref "R8") (pin "2") (pinfunction "2_2") (pintype "passive"))
      (node (ref "U6") (pin "5") (pinfunction "DRV_LO_5") (pintype "output"))
    )
    (net (code "62") (name "Net-(U6-VBOOT)") (class "Default")
      (node (ref "C10") (pin "1") (pinfunction "1_1") (pintype "passive"))
      (node (ref "D4") (pin "C") (pinfunction "C_C") (pintype "passive"))
      (node (ref "U6") (pin "8") (pinfunction "VBOOT_8") (pintype "power_in"))
    )
    (net (code "63") (name "Net-(U7-IN+)") (class "Default")
      (node (ref "C14") (pin "2") (pinfunction "2_2") (pintype "passive"))
      (node (ref "R10") (pin "2") (pinfunction "2_2") (pintype "passive"))
      (node (ref "U7") (pin "4") (pinfunction "IN+_4") (pintype "passive"))
    )
    (net (code "64") (name "Net-(U7-IN-)") (class "Default")
      (node (ref "C14") (pin "1") (pinfunction "1_1") (pintype "passive"))
      (node (ref "R11") (pin "2") (pinfunction "2_2") (pintype "passive"))
      (node (ref "U7") (pin "5") (pinfunction "IN-_5") (pintype "passive"))
    )
    (net (code "65") (name "Net-(U7-OUT)") (class "Default")
      (node (ref "R123") (pin "2") (pinfunction "2_2") (pintype "passive"))
      (node (ref "U7") (pin "6") (pinfunction "OUT_6") (pintype "passive"))
    )
    (net (code "66") (name "SWCLK") (class "Default")
      (node (ref "J4") (pin "4") (pinfunction "4_4") (pintype "passive"))
      (node (ref "U1") (pin "37") (pinfunction "PA14-JTCK-SWCLK_37") (pintype "bidirectional"))
    )
    (net (code "67") (name "SWDIO") (class "Default")
      (node (ref "J4") (pin "6") (pinfunction "6_6") (pintype "passive"))
      (node (ref "U1") (pin "34") (pinfunction "PA13-JTMS-SWDIO_34") (pintype "bidirectional"))
    )
    (net (code "68") (name "UART_RX") (class "Default")
      (node (ref "J4") (pin "1") (pinfunction "1_1") (pintype "passive"))
      (node (ref "U1") (pin "43") (pinfunction "PB7_43") (pintype "bidirectional"))
    )
    (net (code "69") (name "UART_TX") (class "Default")
      (node (ref "J4") (pin "3") (pinfunction "3_3") (pintype "passive"))
      (node (ref "U1") (pin "42") (pinfunction "PB6_42") (pintype "bidirectional"))
    )
    (net (code "70") (name "VCC") (class "Default")
      (node (ref "C1") (pin "+") (pinfunction "+_+") (pintype "passive"))
      (node (ref "C11") (pin "1") (pinfunction "1_1") (pintype "passive"))
      (node (ref "C12") (pin "1") (pinfunction "1_1") (pintype "passive"))
      (node (ref "C2") (pin "+") (pinfunction "+_+") (pintype "passive"))
      (node (ref "C3") (pin "1") (pinfunction "1_1") (pintype "passive"))
      (node (ref "C5") (pin "1") (pinfunction "1_1") (pintype "passive"))
      (node (ref "C6") (pin "1") (pinfunction "1_1") (pintype "passive"))
      (node (ref "Q1") (pin "5") (pinfunction "DRAIN_5") (pintype "passive"))
      (node (ref "Q3") (pin "5") (pinfunction "DRAIN_5") (pintype "passive"))
      (node (ref "R13") (pin "2") (pinfunction "2_2") (pintype "passive"))
      (node (ref "U8") (pin "1") (pinfunction "VI_1") (pintype "input"))
    )
    (net (code "71") (name "VCS") (class "Default")
      (node (ref "C11") (pin "2") (pinfunction "2_2") (pintype "passive"))
      (node (ref "C12") (pin "2") (pinfunction "2_2") (pintype "passive"))
      (node (ref "C13") (pin "2") (pinfunction "2_2") (pintype "passive"))
      (node (ref "C5") (pin "2") (pinfunction "2_2") (pintype "passive"))
      (node (ref "C6") (pin "2") (pinfunction "2_2") (pintype "passive"))
      (node (ref "Q2") (pin "1") (pinfunction "SOURCE_1") (pintype "passive"))
      (node (ref "Q2") (pin "2") (pinfunction "SOURCE_2") (pintype "passive"))
      (node (ref "Q2") (pin "3") (pinfunction "SOURCE_3") (pintype "passive"))
      (node (ref "Q4") (pin "1") (pinfunction "SOURCE_1") (pintype "passive"))
      (node (ref "Q4") (pin "2") (pinfunction "SOURCE_2") (pintype "passive"))
      (node (ref "Q4") (pin "3") (pinfunction "SOURCE_3") (pintype "passive"))
      (node (ref "R7") (pin "1") (pinfunction "1_1") (pintype "passive"))
      (node (ref "R8") (pin "1") (pinfunction "1_1") (pintype "passive"))
      (node (ref "R9") (pin "2$1") (pinfunction "2_2$1") (pintype "passive"))
      (node (ref "R9") (pin "2$2") (pinfunction "2_2$2") (pintype "passive"))
    )
    (net (code "72") (name "VCS_B_N") (class "Default")
      (node (ref "R11") (pin "1") (pinfunction "1_1") (pintype "passive"))
      (node (ref "R9") (pin "1S") (pinfunction "1S_1S") (pintype "passive"))
    )
    (net (code "73") (name "VCS_B_P") (class "Default")
      (node (ref "R10") (pin "1") (pinfunction "1_1") (pintype "passive"))
      (node (ref "R9") (pin "2S") (pinfunction "2S_2S") (pintype "passive"))
    )
    (net (code "74") (name "VSENSE") (class "Default")
      (node (ref "C17") (pin "2") (pinfunction "2_2") (pintype "passive"))
      (node (ref "R13") (pin "1") (pinfunction "1_1") (pintype "passive"))
      (node (ref "R14") (pin "2") (pinfunction "2_2") (pintype "passive"))
      (node (ref "U1") (pin "15") (pinfunction "PA5_15") (pintype "bidirectional"))
    )
    (net (code "75") (name "unconnected-(U1-PA10-Pad31)") (class "Default")
      (node (ref "U1") (pin "31") (pinfunction "PA10_31") (pintype "bidirectional"))
    )
    (net (code "76") (name "unconnected-(U1-PA11-Pad32)") (class "Default")
      (node (ref "U1") (pin "32") (pinfunction "PA11_32") (pintype "bidirectional"))
    )
    (net (code "77") (name "unconnected-(U1-PA12-Pad33)") (class "Default")
      (node (ref "U1") (pin "33") (pinfunction "PA12_33") (pintype "bidirectional"))
    )
    (net (code "78") (name "unconnected-(U1-PA15-JTDI-Pad38)") (class "Default")
      (node (ref "U1") (pin "38") (pinfunction "PA15-JTDI_38") (pintype "bidirectional"))
    )
    (net (code "79") (name "unconnected-(U1-PB3-JTDO-Pad39)") (class "Default")
      (node (ref "U1") (pin "39") (pinfunction "PB3-JTDO_39") (pintype "bidirectional"))
    )
    (net (code "80") (name "unconnected-(U1-PB4-JNTRST-Pad40)") (class "Default")
      (node (ref "U1") (pin "40") (pinfunction "PB4-JNTRST_40") (pintype "bidirectional"))
    )
    (net (code "81") (name "unconnected-(U1-PB5-Pad41)") (class "Default")
      (node (ref "U1") (pin "41") (pinfunction "PB5_41") (pintype "bidirectional"))
    )
    (net (code "82") (name "unconnected-(U1-PB15-Pad28)") (class "Default")
      (node (ref "U1") (pin "28") (pinfunction "PB15_28") (pintype "bidirectional"))
    )
    (net (code "83") (name "unconnected-(U1-PC15-OSC32_OUT-Pad4)") (class "Default")
      (node (ref "U1") (pin "4") (pinfunction "PC15-OSC32_OUT_4") (pintype "bidirectional"))
    )
    (net (code "84") (name "unconnected-(U1-VBAT-Pad1)") (class "Default")
      (node (ref "U1") (pin "1") (pinfunction "VBAT_1") (pintype "passive"))
    )
    (net (code "85") (name "~{EMS_ISO}") (class "Default")
      (node (ref "J1") (pin "6") (pinfunction "6_6") (pintype "input"))
      (node (ref "R28") (pin "2") (pinfunction "2_2") (pintype "passive"))
    )
    (net (code "86") (name "~{EMS}") (class "Default")
      (node (ref "R30") (pin "2") (pinfunction "2_2") (pintype "passive"))
      (node (ref "U1") (pin "2") (pinfunction "PC13-TAMPER-RTC_2") (pintype "bidirectional"))
      (node (ref "U12") (pin "1") (pinfunction "I0_1") (pintype "input"))
      (node (ref "U13") (pin "1") (pinfunction "I0_1") (pintype "input"))
      (node (ref "U14") (pin "1") (pinfunction "I0_1") (pintype "input"))
      (node (ref "U15") (pin "1") (pinfunction "I0_1") (pintype "input"))
      (node (ref "U4") (pin "3") (pinfunction "E_3") (pintype "passive"))
    )
    (net (code "87") (name "~{RESET}") (class "Default")
      (node (ref "C22") (pin "2") (pinfunction "2_2") (pintype "passive"))
      (node (ref "S1") (pin "P$2") (pinfunction "2_P$2") (pintype "bidirectional"))
      (node (ref "U1") (pin "7") (pinfunction "NRST_7") (pintype "bidirectional"))
    )
  )
)
